# power_supply_blk.net
KiCad netlist of a schematic drawn in Altium Designer
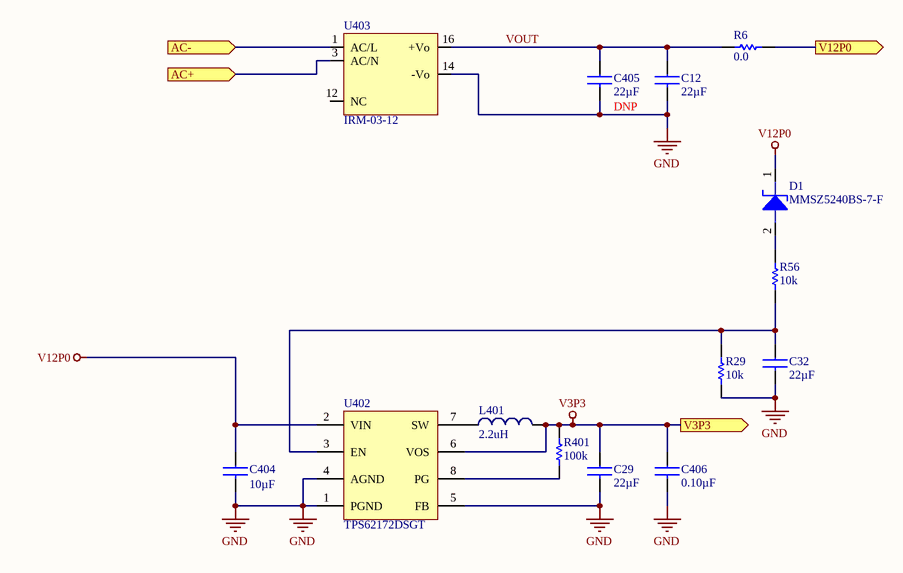
[diagram p0: power_supply_blk.SchDoc]

(export (version "E")
  (design (tool "Eeschema 10.0.6"))
  (components
    (comp (ref "C12")
      (value "22µF")
      (footprint "C0805")
      (description "CAP CER 22UF 16V 20% X5R 0805")
      (fields (field (name "MPN") "GRM219R61C226ME15L"))
      (libsource (lib "Capacitor") (part "GRM219R61C226ME15L"))
    )
    (comp (ref "C29")
      (value "22µF")
      (footprint "C0805")
      (description "CAP CER 22UF 16V X5R 0805")
      (fields (field (name "MPN") "GRM21BR61C226ME44L"))
      (libsource (lib "Capacitor") (part "GRM21BR61C226ME44L"))
    )
    (comp (ref "C32")
      (value "22µF")
      (footprint "C0805")
      (description "CAP CER 22UF 16V 20% X5R 0805")
      (fields (field (name "MPN") "GRM219R61C226ME15L"))
      (libsource (lib "Capacitor") (part "GRM219R61C226ME15L"))
    )
    (comp (ref "C404")
      (value "10µF")
      (footprint "C1206")
      (description "CAP CER 10UF 16V X7R 1206")
      (fields (field (name "MPN") "GRM31CR71C106KAC7L"))
      (libsource (lib "Capacitor") (part "GRM31CR71C106KAC7L"))
    )
    (comp (ref "C405")
      (value "22µF")
      (footprint "C0805")
      (description "CAP CER 22UF 16V X5R 0805")
      (fields (field (name "MPN") "GRM21BR61C226ME44L") (field (name "DNP") "DNP"))
      (libsource (lib "Capacitor") (part "GRM21BR61C226ME44L"))
    )
    (comp (ref "C406")
      (value "0.10µF")
      (footprint "C0402")
      (description "CAP CER 0.1UF 50V X7R 0402")
      (fields (field (name "MPN") "GRM155R71H104ME14D"))
      (libsource (lib "Capacitor") (part "GRM155R71H104ME14D"))
    )
    (comp (ref "D1")
      (value "MMSZ5240BS-7-F")
      (footprint "SOD-323")
      (description "DIODE ZENER 10V 200MW SOD323")
      (fields (field (name "MPN") "MMSZ5240BS-7-F"))
      (libsource (lib "Diode") (part "MMSZ5240BS-7-F"))
    )
    (comp (ref "L401")
      (value "2.2uH")
      (footprint "NR3015")
      (description "FIXED IND 2.2UH 1.5A 72 MOHM SMD")
      (fields (field (name "MPN") "NR3015T2R2M"))
      (libsource (lib "Inductor") (part "NR3015T2R2M"))
    )
    (comp (ref "R6")
      (value "0.0")
      (footprint "R0805")
      (description "RES SMD 0.0 OHM JUMPER 1/8W 0805")
      (fields (field (name "MPN") "9C08052A0R00JLHFT"))
      (libsource (lib "Res") (part "9C08052A0R00JLHFT"))
    )
    (comp (ref "R29")
      (value "10k")
      (footprint "R0603")
      (description "RES SMD 10K OHM 1% 1/16W 0603")
      (fields (field (name "MPN") "ERJ-3EKF1002V") (field (name "Comment") "5-1879337-9"))
      (libsource (lib "Res") (part "5-1879337-9"))
    )
    (comp (ref "R56")
      (value "10k")
      (footprint "R0603")
      (description "RES SMD 10K OHM 1% 1/16W 0603")
      (fields (field (name "MPN") "ERJ-3EKF1002V") (field (name "Comment") "5-1879337-9"))
      (libsource (lib "Res") (part "5-1879337-9"))
    )
    (comp (ref "R401")
      (value "100k")
      (footprint "R0402")
      (description "RES SMD 100K OHM 1% 1/10W 0402")
      (fields (field (name "MPN") "ERJ-2RKF1003X"))
      (libsource (lib "Res") (part "ERJ-2RKF1003X"))
    )
    (comp (ref "U402")
      (value "TPS62172DSGT")
      (footprint "WSON8")
      (description "IC REG BUCK 3.3V 0.5A SYNC 8WSON")
      (fields (field (name "MPN") "TPS62172DSGT"))
      (libsource (lib "IC") (part "TPS62172DSGT"))
    )
    (comp (ref "U403")
      (value "IRM-03-12")
      (footprint "IRM-03-12")
      (description "AC/DC Power Modules 85-305Vac 12Vout 250mA 3W PCM mnt")
      (fields (field (name "MPN") "IRM-03-12"))
      (libsource (lib "WiLamp") (part "IRM-03-12"))
    )
  )
  (nets
    (net (code "1") (name "/AC+") (class "Default")
      (node (ref "U403") (pin "3") (pinfunction "AC/N_3") (pintype "passive"))
    )
    (net (code "2") (name "/AC-") (class "Default")
      (node (ref "U403") (pin "1") (pinfunction "AC/L_1") (pintype "passive"))
    )
    (net (code "3") (name "/VOUT") (class "Default")
      (node (ref "C12") (pin "1") (pinfunction "1_1") (pintype "passive"))
      (node (ref "C405") (pin "1") (pinfunction "1_1") (pintype "passive"))
      (node (ref "R6") (pin "1") (pinfunction "1_1") (pintype "passive"))
      (node (ref "U403") (pin "16") (pinfunction "+Vo_16") (pintype "passive"))
    )
    (net (code "4") (name "GND") (class "Default")
      (node (ref "C12") (pin "2") (pinfunction "2_2") (pintype "passive"))
      (node (ref "C29") (pin "2") (pinfunction "2_2") (pintype "passive"))
      (node (ref "C32") (pin "2") (pinfunction "2_2") (pintype "passive"))
      (node (ref "C404") (pin "2") (pinfunction "2_2") (pintype "passive"))
      (node (ref "C405") (pin "2") (pinfunction "2_2") (pintype "passive"))
      (node (ref "C406") (pin "2") (pinfunction "2_2") (pintype "passive"))
      (node (ref "R29") (pin "2") (pinfunction "2_2") (pintype "passive"))
      (node (ref "U402") (pin "1") (pinfunction "PGND_1") (pintype "passive"))
      (node (ref "U402") (pin "4") (pinfunction "AGND_4") (pintype "passive"))
      (node (ref "U402") (pin "5") (pinfunction "FB_5") (pintype "passive"))
      (node (ref "U403") (pin "14") (pinfunction "-Vo_14") (pintype "passive"))
    )
    (net (code "5") (name "Net-(D1-A)") (class "Default")
      (node (ref "D1") (pin "2") (pinfunction "A_2") (pintype "passive"))
      (node (ref "R56") (pin "1") (pinfunction "1_1") (pintype "passive"))
    )
    (net (code "6") (name "Net-(U402-EN)") (class "Default")
      (node (ref "C32") (pin "1") (pinfunction "1_1") (pintype "passive"))
      (node (ref "R29") (pin "1") (pinfunction "1_1") (pintype "passive"))
      (node (ref "R56") (pin "2") (pinfunction "2_2") (pintype "passive"))
      (node (ref "U402") (pin "3") (pinfunction "EN_3") (pintype "passive"))
    )
    (net (code "7") (name "Net-(U402-PG)") (class "Default")
      (node (ref "R401") (pin "1") (pinfunction "1_1") (pintype "passive"))
      (node (ref "U402") (pin "8") (pinfunction "PG_8") (pintype "passive"))
    )
    (net (code "8") (name "Net-(U402-SW)") (class "Default")
      (node (ref "L401") (pin "1") (pinfunction "1_1") (pintype "passive"))
      (node (ref "U402") (pin "7") (pinfunction "SW_7") (pintype "passive"))
    )
    (net (code "9") (name "V3P3") (class "Default")
      (node (ref "C29") (pin "1") (pinfunction "1_1") (pintype "passive"))
      (node (ref "C406") (pin "1") (pinfunction "1_1") (pintype "passive"))
      (node (ref "L401") (pin "2") (pinfunction "2_2") (pintype "passive"))
      (node (ref "R401") (pin "2") (pinfunction "2_2") (pintype "passive"))
      (node (ref "U402") (pin "6") (pinfunction "VOS_6") (pintype "passive"))
    )
    (net (code "10") (name "V12P0") (class "Default")
      (node (ref "C404") (pin "1") (pinfunction "1_1") (pintype "passive"))
      (node (ref "D1") (pin "1") (pinfunction "K_1") (pintype "passive"))
      (node (ref "R6") (pin "2") (pinfunction "2_2") (pintype "passive"))
      (node (ref "U402") (pin "2") (pinfunction "VIN_2") (pintype "passive"))
    )
    (net (code "11") (name "unconnected-(U403-NC-Pad12)") (class "Default")
      (node (ref "U403") (pin "12") (pinfunction "NC_12") (pintype "passive"))
    )
  )
)
